# CAN_transceiver.net
KiCad netlist of a schematic drawn in Altium Designer
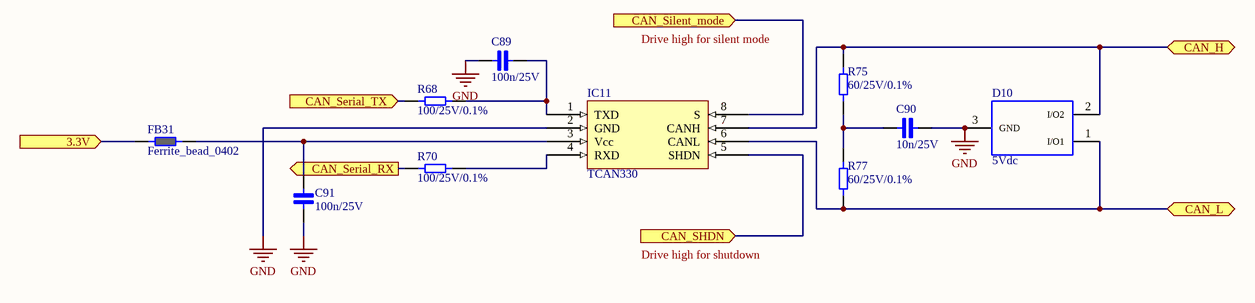
[diagram p0: CAN_transceiver.SchDoc]

(export (version "E")
  (design (tool "Eeschema 10.0.6"))
  (components
    (comp (ref "C89")
      (value "100n/25V")
      (footprint "Cap_0402")
      (description "Ceramic Capacitor 100n / 0402 / 25V / ±5%, Wurth Elektronik MLCC")
      (libsource (lib "") (part "Cap_0402_100n_1"))
    )
    (comp (ref "C90")
      (value "10n/25V")
      (footprint "Cap_0402")
      (description "Ceramic Capacitor 10n / 0402 / 25V / ±5%, Wurth Elektronik MLCC")
      (libsource (lib "Cubesat_lib") (part "Cap_0402_10n"))
    )
    (comp (ref "C91")
      (value "100n/25V")
      (footprint "Cap_0402")
      (description "Ceramic Capacitor 100n / 0402 / 25V / ±5%, Wurth Elektronik MLCC")
      (libsource (lib "Cubesat_lib") (part "Cap_0402_100n"))
    )
    (comp (ref "D10")
      (value "5Vdc")
      (footprint "WE-TVS_SOT23-3L")
      (description "WE-TVS TVS Diode - Standard Series, SOT23-3L, 2Channel, 5Vdc")
      (fields
        (field (name "MANUFACTURER PART NUMBER") "824022")
        (field (name "MANUFACTURER") "Wurth Elektronik")
      )
      (libsource (lib "WE-TVS_standard_tvs") (part "824022"))
    )
    (comp (ref "FB31")
      (value "Ferrite_bead_0402")
      (footprint "FERRITE_0402")
      (description "Ferrite bead, wurth 74269241102")
      (libsource (lib "Cubesat_lib") (part "Ferrite_bead_0402"))
    )
    (comp (ref "IC11")
      (value "TCAN330")
      (footprint "SOIC8")
      (description "CAN transceiver, 3,3V")
      (libsource (lib "Cubesat_lib") (part "TCAN330"))
    )
    (comp (ref "R68")
      (value "100/25V/0.1%")
      (footprint "RES_0402")
      (description "Vishay, thin film resistor 100/25V/0.1%")
      (libsource (lib "Cubesat_lib") (part "Res_0402_100"))
    )
    (comp (ref "R70")
      (value "100/25V/0.1%")
      (footprint "RES_0402")
      (description "Vishay, thin film resistor 100/25V/0.1%")
      (libsource (lib "Cubesat_lib") (part "Res_0402_100"))
    )
    (comp (ref "R75")
      (value "60/25V/0.1%")
      (footprint "RES_1206")
      (description "Vishay, thin film resistor 60/25V/0.1%")
      (libsource (lib "Cubesat_lib") (part "Res_1206_60"))
    )
    (comp (ref "R77")
      (value "60/25V/0.1%")
      (footprint "RES_1206")
      (description "Vishay, thin film resistor 60/25V/0.1%")
      (libsource (lib "Cubesat_lib") (part "Res_1206_60"))
    )
  )
  (nets
    (net (code "1") (name "/3.3V") (class "Default")
      (node (ref "FB31") (pin "1") (pinfunction "1_1") (pintype "passive"))
    )
    (net (code "2") (name "/CAN_H") (class "Default")
      (node (ref "D10") (pin "2") (pinfunction "I/O2_2") (pintype "passive"))
      (node (ref "IC11") (pin "7") (pinfunction "CANH_7") (pintype "input"))
      (node (ref "R75") (pin "2") (pinfunction "2_2") (pintype "passive"))
    )
    (net (code "3") (name "/CAN_L") (class "Default")
      (node (ref "D10") (pin "1") (pinfunction "I/O1_1") (pintype "passive"))
      (node (ref "IC11") (pin "6") (pinfunction "CANL_6") (pintype "input"))
      (node (ref "R77") (pin "1") (pinfunction "1_1") (pintype "passive"))
    )
    (net (code "4") (name "/CAN_SHDN") (class "Default")
      (node (ref "IC11") (pin "5") (pinfunction "SHDN_5") (pintype "input"))
    )
    (net (code "5") (name "/CAN_Serial_RX") (class "Default")
      (node (ref "R70") (pin "1") (pinfunction "1_1") (pintype "passive"))
    )
    (net (code "6") (name "/CAN_Serial_TX") (class "Default")
      (node (ref "R68") (pin "1") (pinfunction "1_1") (pintype "passive"))
    )
    (net (code "7") (name "/CAN_Silent_mode") (class "Default")
      (node (ref "IC11") (pin "8") (pinfunction "S_8") (pintype "input"))
    )
    (net (code "8") (name "GND") (class "Default")
      (node (ref "C89") (pin "1") (pinfunction "1_1") (pintype "passive"))
      (node (ref "C90") (pin "2") (pinfunction "2_2") (pintype "passive"))
      (node (ref "C91") (pin "1") (pinfunction "1_1") (pintype "passive"))
      (node (ref "D10") (pin "3") (pinfunction "GND_3") (pintype "passive"))
      (node (ref "IC11") (pin "2") (pinfunction "GND_2") (pintype "input"))
    )
    (net (code "9") (name "Net-(C90-Pad1)") (class "Default")
      (node (ref "C90") (pin "1") (pinfunction "1_1") (pintype "passive"))
      (node (ref "R75") (pin "1") (pinfunction "1_1") (pintype "passive"))
      (node (ref "R77") (pin "2") (pinfunction "2_2") (pintype "passive"))
    )
    (net (code "10") (name "Net-(IC11-RXD)") (class "Default")
      (node (ref "IC11") (pin "4") (pinfunction "RXD_4") (pintype "input"))
      (node (ref "R70") (pin "2") (pinfunction "2_2") (pintype "passive"))
    )
    (net (code "11") (name "Net-(IC11-TXD)") (class "Default")
      (node (ref "C89") (pin "2") (pinfunction "2_2") (pintype "passive"))
      (node (ref "IC11") (pin "1") (pinfunction "TXD_1") (pintype "input"))
      (node (ref "R68") (pin "2") (pinfunction "2_2") (pintype "passive"))
    )
    (net (code "12") (name "Net-(IC11-Vcc)") (class "Default")
      (node (ref "C91") (pin "2") (pinfunction "2_2") (pintype "passive"))
      (node (ref "FB31") (pin "2") (pinfunction "2_2") (pintype "passive"))
      (node (ref "IC11") (pin "3") (pinfunction "Vcc_3") (pintype "input"))
    )
  )
)
